# 08E-005.net
KiCad netlist of a schematic drawn in EAGLE
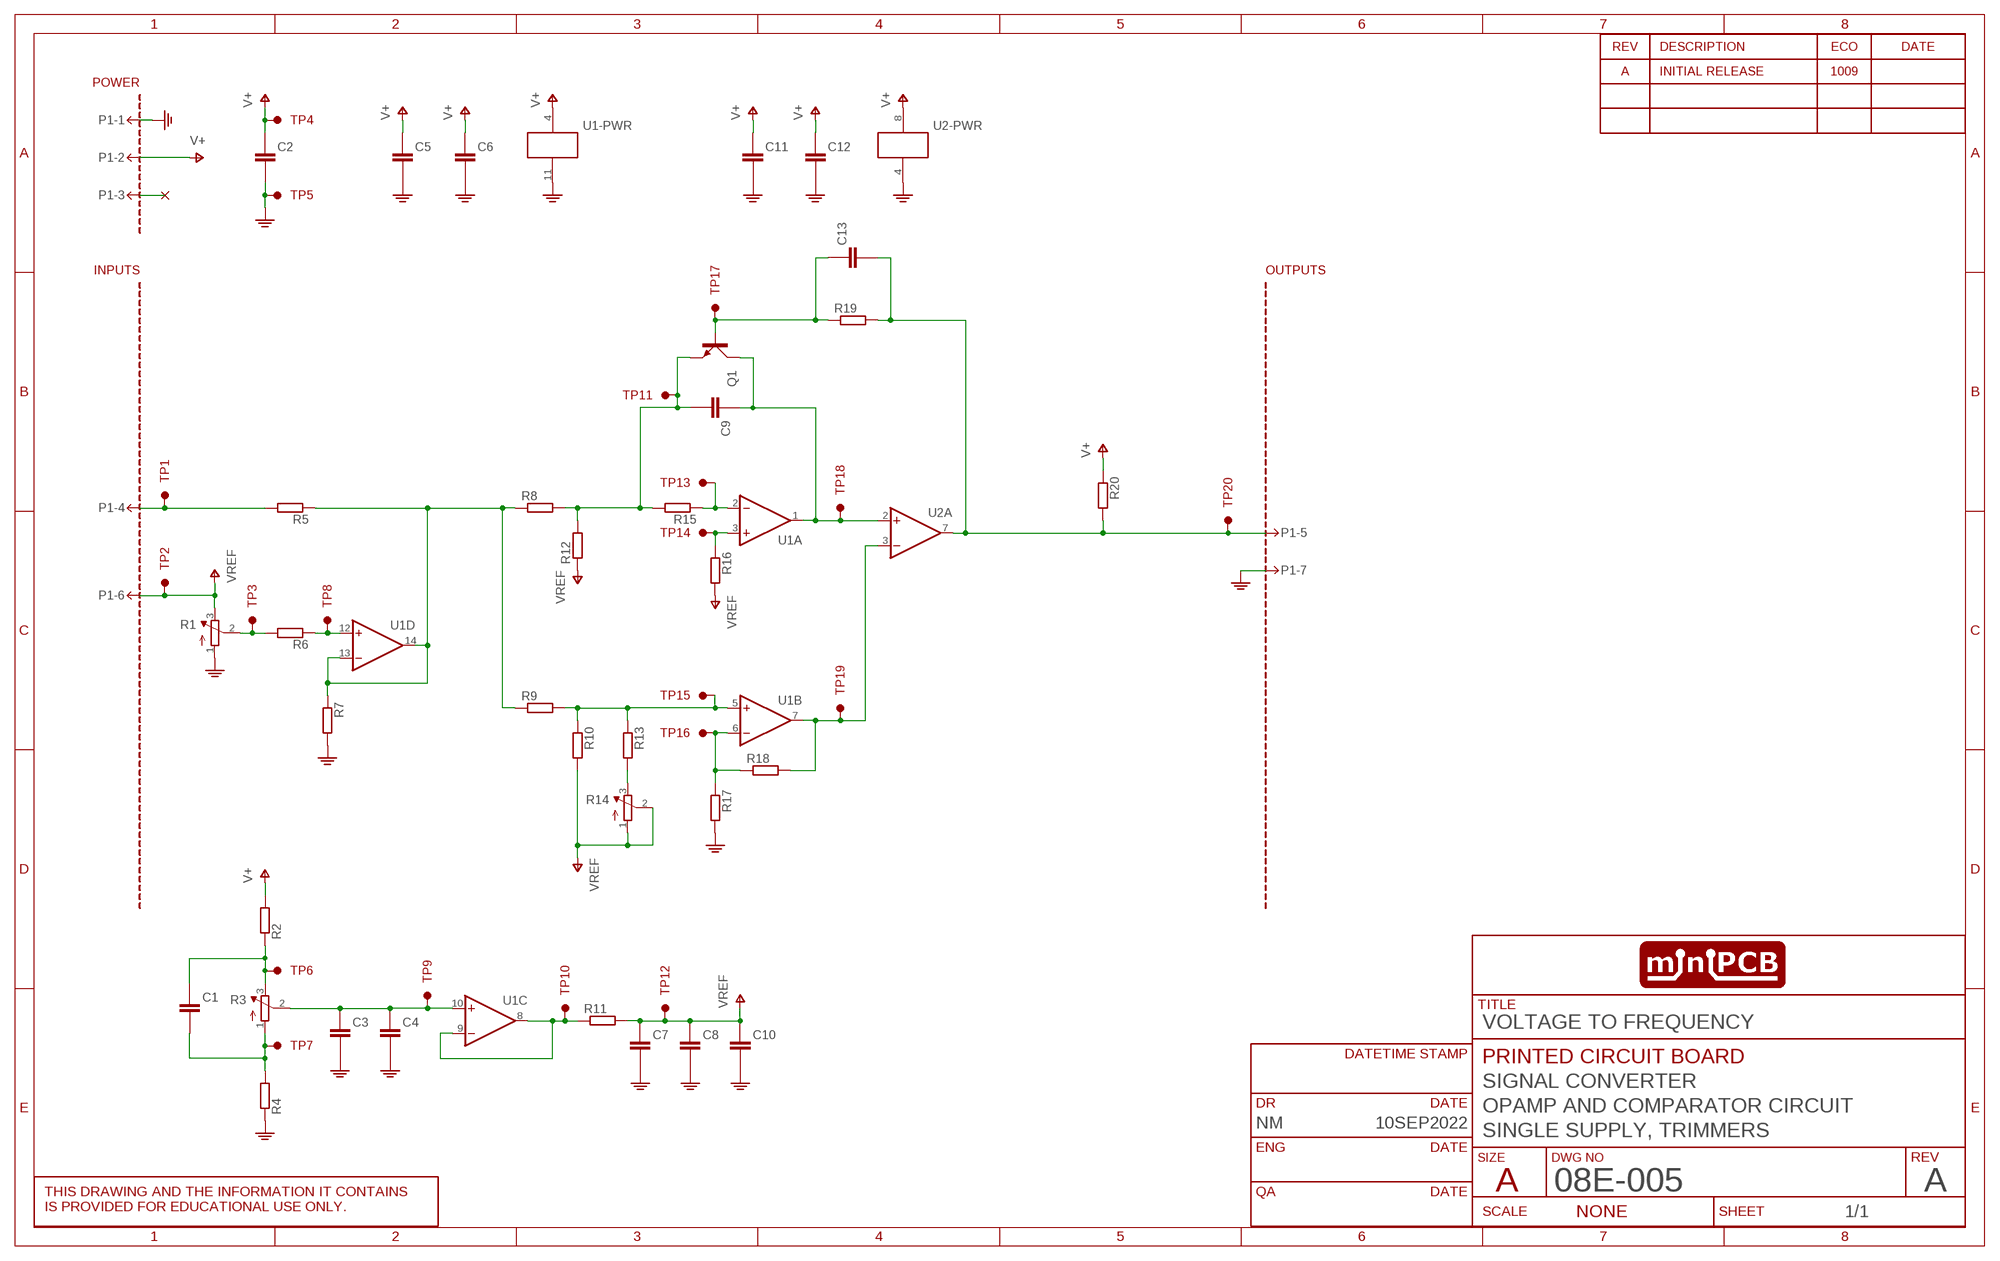
[diagram p0: schematic, sheet 1]

(export (version "E")
  (design (tool "Eeschema 10.0.6"))
  (components
    (comp (ref "C1")
      (value "CAPACITORTHD")
      (footprint "eagle-import:C050-024X044")
      (libsource (lib "eagle-import") (part "CAPACITORTHD"))
    )
    (comp (ref "C2")
      (value "CAPACITOR_10")
      (footprint "eagle-import:C5MM")
      (libsource (lib "eagle-import") (part "CAPACITOR_10"))
    )
    (comp (ref "C3")
      (value "CAPACITORTHD")
      (footprint "eagle-import:C050-024X044")
      (libsource (lib "eagle-import") (part "CAPACITORTHD"))
    )
    (comp (ref "C4")
      (value "CAPACITORTHD")
      (footprint "eagle-import:C050-024X044")
      (libsource (lib "eagle-import") (part "CAPACITORTHD"))
    )
    (comp (ref "C5")
      (value "CAPACITORTHD")
      (footprint "eagle-import:C050-024X044")
      (libsource (lib "eagle-import") (part "CAPACITORTHD"))
    )
    (comp (ref "C6")
      (value "CAPACITORTHD")
      (footprint "eagle-import:C050-024X044")
      (libsource (lib "eagle-import") (part "CAPACITORTHD"))
    )
    (comp (ref "C7")
      (value "CAPACITORTHD")
      (footprint "eagle-import:C050-024X044")
      (libsource (lib "eagle-import") (part "CAPACITORTHD"))
    )
    (comp (ref "C8")
      (value "CAPACITORTHD")
      (footprint "eagle-import:C050-024X044")
      (libsource (lib "eagle-import") (part "CAPACITORTHD"))
    )
    (comp (ref "C9")
      (value "CAPACITORTHD")
      (footprint "eagle-import:C050-024X044")
      (libsource (lib "eagle-import") (part "CAPACITORTHD"))
    )
    (comp (ref "C10")
      (value "CAPACITOR_10")
      (footprint "eagle-import:C5MM")
      (libsource (lib "eagle-import") (part "CAPACITOR_10"))
    )
    (comp (ref "C11")
      (value "CAPACITORTHD")
      (footprint "eagle-import:C050-024X044")
      (libsource (lib "eagle-import") (part "CAPACITORTHD"))
    )
    (comp (ref "C12")
      (value "CAPACITORTHD")
      (footprint "eagle-import:C050-024X044")
      (libsource (lib "eagle-import") (part "CAPACITORTHD"))
    )
    (comp (ref "C13")
      (value "CAPACITORTHD")
      (footprint "eagle-import:C050-024X044")
      (libsource (lib "eagle-import") (part "CAPACITORTHD"))
    )
    (comp (ref "P1-")
      (value "MINIPCB_7P50X100")
      (footprint "eagle-import:MINIPCB_7P_50X100")
      (fields (field (name "PART_NUMBER") "X08E-005-A"))
      (libsource (lib "eagle-import") (part "MINIPCB_7P50X100"))
    )
    (comp (ref "Q1")
      (value "BJT_NPNEBC")
      (footprint "eagle-import:TO92-EBC-OVAL")
      (libsource (lib "eagle-import") (part "BJT_NPNEBC"))
    )
    (comp (ref "R1")
      (value "TRIMPOT3386")
      (footprint "eagle-import:TRIM-3386")
      (libsource (lib "eagle-import") (part "TRIMPOT3386"))
    )
    (comp (ref "R2")
      (value "RESISTOR10MM")
      (footprint "eagle-import:0207_10")
      (libsource (lib "eagle-import") (part "RESISTOR10MM"))
    )
    (comp (ref "R3")
      (value "TRIMPOT0.100THD")
      (footprint "eagle-import:TRIM_0100")
      (libsource (lib "eagle-import") (part "TRIMPOT0.100THD"))
    )
    (comp (ref "R4")
      (value "RESISTOR10MM")
      (footprint "eagle-import:0207_10")
      (libsource (lib "eagle-import") (part "RESISTOR10MM"))
    )
    (comp (ref "R5")
      (value "RESISTOR10MM")
      (footprint "eagle-import:0207_10")
      (libsource (lib "eagle-import") (part "RESISTOR10MM"))
    )
    (comp (ref "R6")
      (value "RESISTOR10MM")
      (footprint "eagle-import:0207_10")
      (libsource (lib "eagle-import") (part "RESISTOR10MM"))
    )
    (comp (ref "R7")
      (value "RESISTOR10MM")
      (footprint "eagle-import:0207_10")
      (libsource (lib "eagle-import") (part "RESISTOR10MM"))
    )
    (comp (ref "R8")
      (value "RESISTOR10MM")
      (footprint "eagle-import:0207_10")
      (libsource (lib "eagle-import") (part "RESISTOR10MM"))
    )
    (comp (ref "R9")
      (value "RESISTOR10MM")
      (footprint "eagle-import:0207_10")
      (libsource (lib "eagle-import") (part "RESISTOR10MM"))
    )
    (comp (ref "R10")
      (value "RESISTOR10MM")
      (footprint "eagle-import:0207_10")
      (libsource (lib "eagle-import") (part "RESISTOR10MM"))
    )
    (comp (ref "R11")
      (value "RESISTOR10MM")
      (footprint "eagle-import:0207_10")
      (libsource (lib "eagle-import") (part "RESISTOR10MM"))
    )
    (comp (ref "R12")
      (value "RESISTOR10MM")
      (footprint "eagle-import:0207_10")
      (libsource (lib "eagle-import") (part "RESISTOR10MM"))
    )
    (comp (ref "R13")
      (value "RESISTOR10MM")
      (footprint "eagle-import:0207_10")
      (libsource (lib "eagle-import") (part "RESISTOR10MM"))
    )
    (comp (ref "R14")
      (value "TRIMPOT0.100THD")
      (footprint "eagle-import:TRIM_0100")
      (libsource (lib "eagle-import") (part "TRIMPOT0.100THD"))
    )
    (comp (ref "R15")
      (value "RESISTOR10MM")
      (footprint "eagle-import:0207_10")
      (libsource (lib "eagle-import") (part "RESISTOR10MM"))
    )
    (comp (ref "R16")
      (value "RESISTOR10MM")
      (footprint "eagle-import:0207_10")
      (libsource (lib "eagle-import") (part "RESISTOR10MM"))
    )
    (comp (ref "R17")
      (value "RESISTOR10MM")
      (footprint "eagle-import:0207_10")
      (libsource (lib "eagle-import") (part "RESISTOR10MM"))
    )
    (comp (ref "R18")
      (value "RESISTOR10MM")
      (footprint "eagle-import:0207_10")
      (libsource (lib "eagle-import") (part "RESISTOR10MM"))
    )
    (comp (ref "R19")
      (value "RESISTOR10MM")
      (footprint "eagle-import:0207_10")
      (libsource (lib "eagle-import") (part "RESISTOR10MM"))
    )
    (comp (ref "R20")
      (value "RESISTOR10MM")
      (footprint "eagle-import:0207_10")
      (libsource (lib "eagle-import") (part "RESISTOR10MM"))
    )
    (comp (ref "TP1")
      (value "TESTPOINTKE5000-SMTEXT")
      (footprint "eagle-import:PINS_1_TESTPOINT_KE5000_NOTEXT")
      (libsource (lib "eagle-import") (part "TESTPOINTKE5000-SMTEXT"))
    )
    (comp (ref "TP2")
      (value "TESTPOINTKE5000-SMTEXT")
      (footprint "eagle-import:PINS_1_TESTPOINT_KE5000_NOTEXT")
      (libsource (lib "eagle-import") (part "TESTPOINTKE5000-SMTEXT"))
    )
    (comp (ref "TP3")
      (value "TESTPOINTKE5000-SMTEXT")
      (footprint "eagle-import:PINS_1_TESTPOINT_KE5000_NOTEXT")
      (libsource (lib "eagle-import") (part "TESTPOINTKE5000-SMTEXT"))
    )
    (comp (ref "TP4")
      (value "TESTPOINTKE5000-SMTEXT")
      (footprint "eagle-import:PINS_1_TESTPOINT_KE5000_NOTEXT")
      (libsource (lib "eagle-import") (part "TESTPOINTKE5000-SMTEXT"))
    )
    (comp (ref "TP5")
      (value "TESTPOINTKE5000-SMTEXT")
      (footprint "eagle-import:PINS_1_TESTPOINT_KE5000_NOTEXT")
      (libsource (lib "eagle-import") (part "TESTPOINTKE5000-SMTEXT"))
    )
    (comp (ref "TP6")
      (value "TESTPOINTKE5000-SMTEXT")
      (footprint "eagle-import:PINS_1_TESTPOINT_KE5000_NOTEXT")
      (libsource (lib "eagle-import") (part "TESTPOINTKE5000-SMTEXT"))
    )
    (comp (ref "TP7")
      (value "TESTPOINTKE5000-SMTEXT")
      (footprint "eagle-import:PINS_1_TESTPOINT_KE5000_NOTEXT")
      (libsource (lib "eagle-import") (part "TESTPOINTKE5000-SMTEXT"))
    )
    (comp (ref "TP8")
      (value "TESTPOINTKE5000-SMTEXT")
      (footprint "eagle-import:PINS_1_TESTPOINT_KE5000_NOTEXT")
      (libsource (lib "eagle-import") (part "TESTPOINTKE5000-SMTEXT"))
    )
    (comp (ref "TP9")
      (value "TESTPOINTKE5000-SMTEXT")
      (footprint "eagle-import:PINS_1_TESTPOINT_KE5000_NOTEXT")
      (libsource (lib "eagle-import") (part "TESTPOINTKE5000-SMTEXT"))
    )
    (comp (ref "TP10")
      (value "TESTPOINTKE5000-SMTEXT")
      (footprint "eagle-import:PINS_1_TESTPOINT_KE5000_NOTEXT")
      (libsource (lib "eagle-import") (part "TESTPOINTKE5000-SMTEXT"))
    )
    (comp (ref "TP11")
      (value "TESTPOINTKE5000-SMTEXT")
      (footprint "eagle-import:PINS_1_TESTPOINT_KE5000_NOTEXT")
      (libsource (lib "eagle-import") (part "TESTPOINTKE5000-SMTEXT"))
    )
    (comp (ref "TP12")
      (value "TESTPOINTKE5000-SMTEXT")
      (footprint "eagle-import:PINS_1_TESTPOINT_KE5000_NOTEXT")
      (libsource (lib "eagle-import") (part "TESTPOINTKE5000-SMTEXT"))
    )
    (comp (ref "TP13")
      (value "TESTPOINTKE5000-SMTEXT")
      (footprint "eagle-import:PINS_1_TESTPOINT_KE5000_NOTEXT")
      (libsource (lib "eagle-import") (part "TESTPOINTKE5000-SMTEXT"))
    )
    (comp (ref "TP14")
      (value "TESTPOINTKE5000-SMTEXT")
      (footprint "eagle-import:PINS_1_TESTPOINT_KE5000_NOTEXT")
      (libsource (lib "eagle-import") (part "TESTPOINTKE5000-SMTEXT"))
    )
    (comp (ref "TP15")
      (value "TESTPOINTKE5000-SMTEXT")
      (footprint "eagle-import:PINS_1_TESTPOINT_KE5000_NOTEXT")
      (libsource (lib "eagle-import") (part "TESTPOINTKE5000-SMTEXT"))
    )
    (comp (ref "TP16")
      (value "TESTPOINTKE5000-SMTEXT")
      (footprint "eagle-import:PINS_1_TESTPOINT_KE5000_NOTEXT")
      (libsource (lib "eagle-import") (part "TESTPOINTKE5000-SMTEXT"))
    )
    (comp (ref "TP17")
      (value "TESTPOINTKE5000-SMTEXT")
      (footprint "eagle-import:PINS_1_TESTPOINT_KE5000_NOTEXT")
      (libsource (lib "eagle-import") (part "TESTPOINTKE5000-SMTEXT"))
    )
    (comp (ref "TP18")
      (value "TESTPOINTKE5000-SMTEXT")
      (footprint "eagle-import:PINS_1_TESTPOINT_KE5000_NOTEXT")
      (libsource (lib "eagle-import") (part "TESTPOINTKE5000-SMTEXT"))
    )
    (comp (ref "TP19")
      (value "TESTPOINTKE5000-SMTEXT")
      (footprint "eagle-import:PINS_1_TESTPOINT_KE5000_NOTEXT")
      (libsource (lib "eagle-import") (part "TESTPOINTKE5000-SMTEXT"))
    )
    (comp (ref "TP20")
      (value "TESTPOINTKE5000-SMTEXT")
      (footprint "eagle-import:PINS_1_TESTPOINT_KE5000_NOTEXT")
      (libsource (lib "eagle-import") (part "TESTPOINTKE5000-SMTEXT"))
    )
    (comp (ref "U1")
      (value "OPAMP_QUADTHD")
      (footprint "eagle-import:DIL14")
      (libsource (lib "eagle-import") (part "OPAMP_QUADTHD"))
    )
    (comp (ref "U2")
      (value "COMPARATOR_SINGLE_WITHBALANCETHD")
      (footprint "eagle-import:DIL08")
      (libsource (lib "eagle-import") (part "COMPARATOR_SINGLE_WITHBALANCETHD"))
    )
  )
  (nets
    (net (code "1") (name "GND") (class "Default")
      (node (ref "C10") (pin "-") (pinfunction "-_-") (pintype "passive"))
      (node (ref "C11") (pin "2") (pinfunction "-_2") (pintype "passive"))
      (node (ref "C12") (pin "2") (pinfunction "-_2") (pintype "passive"))
      (node (ref "C2") (pin "-") (pinfunction "-_-") (pintype "passive"))
      (node (ref "C3") (pin "2") (pinfunction "-_2") (pintype "passive"))
      (node (ref "C4") (pin "2") (pinfunction "-_2") (pintype "passive"))
      (node (ref "C5") (pin "2") (pinfunction "-_2") (pintype "passive"))
      (node (ref "C6") (pin "2") (pinfunction "-_2") (pintype "passive"))
      (node (ref "C7") (pin "2") (pinfunction "-_2") (pintype "passive"))
      (node (ref "C8") (pin "2") (pinfunction "-_2") (pintype "passive"))
      (node (ref "P1-") (pin "1") (pinfunction "1_1") (pintype "bidirectional"))
      (node (ref "P1-") (pin "7") (pinfunction "1_7") (pintype "bidirectional"))
      (node (ref "R1") (pin "1") (pinfunction "A_1") (pintype "passive"))
      (node (ref "R17") (pin "2") (pinfunction "2_2") (pintype "passive"))
      (node (ref "R4") (pin "1") (pinfunction "1_1") (pintype "passive"))
      (node (ref "R7") (pin "2") (pinfunction "2_2") (pintype "passive"))
      (node (ref "TP5") (pin "1") (pinfunction "1_1") (pintype "bidirectional"))
      (node (ref "U1") (pin "11") (pinfunction "V-_11") (pintype "power_in"))
      (node (ref "U2") (pin "4") (pinfunction "V-_4") (pintype "power_in"))
    )
    (net (code "2") (name "Net-(C1-+)") (class "Default")
      (node (ref "C1") (pin "1") (pinfunction "+_1") (pintype "passive"))
      (node (ref "R2") (pin "1") (pinfunction "1_1") (pintype "passive"))
      (node (ref "R3") (pin "3") (pinfunction "E_3") (pintype "passive"))
      (node (ref "TP6") (pin "1") (pinfunction "1_1") (pintype "bidirectional"))
    )
    (net (code "3") (name "Net-(C1--)") (class "Default")
      (node (ref "C1") (pin "2") (pinfunction "-_2") (pintype "passive"))
      (node (ref "R3") (pin "1") (pinfunction "A_1") (pintype "passive"))
      (node (ref "R4") (pin "2") (pinfunction "2_2") (pintype "passive"))
      (node (ref "TP7") (pin "1") (pinfunction "1_1") (pintype "bidirectional"))
    )
    (net (code "4") (name "Net-(C3-+)") (class "Default")
      (node (ref "C3") (pin "1") (pinfunction "+_1") (pintype "passive"))
      (node (ref "C4") (pin "1") (pinfunction "+_1") (pintype "passive"))
      (node (ref "R3") (pin "2") (pinfunction "S_2") (pintype "passive"))
      (node (ref "TP9") (pin "1") (pinfunction "1_1") (pintype "bidirectional"))
      (node (ref "U1") (pin "10") (pinfunction "+IN_10") (pintype "input"))
    )
    (net (code "5") (name "Net-(C9-+)") (class "Default")
      (node (ref "C9") (pin "1") (pinfunction "+_1") (pintype "passive"))
      (node (ref "Q1") (pin "C") (pinfunction "C_C") (pintype "passive"))
      (node (ref "TP18") (pin "1") (pinfunction "1_1") (pintype "bidirectional"))
      (node (ref "U1") (pin "1") (pinfunction "OUT_1") (pintype "output"))
      (node (ref "U2") (pin "2") (pinfunction "+IN_2") (pintype "input"))
    )
    (net (code "6") (name "Net-(C9--)") (class "Default")
      (node (ref "C9") (pin "2") (pinfunction "-_2") (pintype "passive"))
      (node (ref "Q1") (pin "E") (pinfunction "E_E") (pintype "passive"))
      (node (ref "R12") (pin "2") (pinfunction "2_2") (pintype "passive"))
      (node (ref "R15") (pin "2") (pinfunction "2_2") (pintype "passive"))
      (node (ref "R8") (pin "2") (pinfunction "2_2") (pintype "passive"))
      (node (ref "TP11") (pin "1") (pinfunction "1_1") (pintype "bidirectional"))
    )
    (net (code "7") (name "Net-(C13-+)") (class "Default")
      (node (ref "C13") (pin "1") (pinfunction "+_1") (pintype "passive"))
      (node (ref "Q1") (pin "B") (pinfunction "B_B") (pintype "passive"))
      (node (ref "R19") (pin "1") (pinfunction "1_1") (pintype "passive"))
      (node (ref "TP17") (pin "1") (pinfunction "1_1") (pintype "bidirectional"))
    )
    (net (code "8") (name "Net-(C13--)") (class "Default")
      (node (ref "C13") (pin "2") (pinfunction "-_2") (pintype "passive"))
      (node (ref "P1-") (pin "5") (pinfunction "1_5") (pintype "bidirectional"))
      (node (ref "R19") (pin "2") (pinfunction "2_2") (pintype "passive"))
      (node (ref "R20") (pin "2") (pinfunction "2_2") (pintype "passive"))
      (node (ref "TP20") (pin "1") (pinfunction "1_1") (pintype "bidirectional"))
      (node (ref "U2") (pin "7") (pinfunction "OUT_7") (pintype "output"))
    )
    (net (code "9") (name "Net-(P1-D-1)") (class "Default")
      (node (ref "P1-") (pin "4") (pinfunction "1_4") (pintype "bidirectional"))
      (node (ref "R5") (pin "2") (pinfunction "2_2") (pintype "passive"))
      (node (ref "TP1") (pin "1") (pinfunction "1_1") (pintype "bidirectional"))
    )
    (net (code "10") (name "Net-(R1-S)") (class "Default")
      (node (ref "R1") (pin "2") (pinfunction "S_2") (pintype "passive"))
      (node (ref "R6") (pin "2") (pinfunction "2_2") (pintype "passive"))
      (node (ref "TP3") (pin "1") (pinfunction "1_1") (pintype "bidirectional"))
    )
    (net (code "11") (name "Net-(R14-E)") (class "Default")
      (node (ref "R13") (pin "2") (pinfunction "2_2") (pintype "passive"))
      (node (ref "R14") (pin "3") (pinfunction "E_3") (pintype "passive"))
    )
    (net (code "12") (name "Net-(U1B-+IN)") (class "Default")
      (node (ref "R16") (pin "1") (pinfunction "1_1") (pintype "passive"))
      (node (ref "TP14") (pin "1") (pinfunction "1_1") (pintype "bidirectional"))
      (node (ref "U1") (pin "3") (pinfunction "+IN_3") (pintype "input"))
    )
    (net (code "13") (name "Net-(U1B--IN)") (class "Default")
      (node (ref "R15") (pin "1") (pinfunction "1_1") (pintype "passive"))
      (node (ref "TP13") (pin "1") (pinfunction "1_1") (pintype "bidirectional"))
      (node (ref "U1") (pin "2") (pinfunction "-IN_2") (pintype "input"))
    )
    (net (code "14") (name "Net-(U1C-+IN)") (class "Default")
      (node (ref "R10") (pin "1") (pinfunction "1_1") (pintype "passive"))
      (node (ref "R13") (pin "1") (pinfunction "1_1") (pintype "passive"))
      (node (ref "R9") (pin "2") (pinfunction "2_2") (pintype "passive"))
      (node (ref "TP15") (pin "1") (pinfunction "1_1") (pintype "bidirectional"))
      (node (ref "U1") (pin "5") (pinfunction "+IN_5") (pintype "input"))
    )
    (net (code "15") (name "Net-(U1C--IN)") (class "Default")
      (node (ref "R17") (pin "1") (pinfunction "1_1") (pintype "passive"))
      (node (ref "R18") (pin "1") (pinfunction "1_1") (pintype "passive"))
      (node (ref "TP16") (pin "1") (pinfunction "1_1") (pintype "bidirectional"))
      (node (ref "U1") (pin "6") (pinfunction "-IN_6") (pintype "input"))
    )
    (net (code "16") (name "Net-(U1C-OUT)") (class "Default")
      (node (ref "R18") (pin "2") (pinfunction "2_2") (pintype "passive"))
      (node (ref "TP19") (pin "1") (pinfunction "1_1") (pintype "bidirectional"))
      (node (ref "U1") (pin "7") (pinfunction "OUT_7") (pintype "output"))
      (node (ref "U2") (pin "3") (pinfunction "-IN_3") (pintype "input"))
    )
    (net (code "17") (name "Net-(U1D--IN)") (class "Default")
      (node (ref "R11") (pin "1") (pinfunction "1_1") (pintype "passive"))
      (node (ref "TP10") (pin "1") (pinfunction "1_1") (pintype "bidirectional"))
      (node (ref "U1") (pin "8") (pinfunction "OUT_8") (pintype "output"))
      (node (ref "U1") (pin "9") (pinfunction "-IN_9") (pintype "input"))
    )
    (net (code "18") (name "Net-(U1E-+IN)") (class "Default")
      (node (ref "R6") (pin "1") (pinfunction "1_1") (pintype "passive"))
      (node (ref "TP8") (pin "1") (pinfunction "1_1") (pintype "bidirectional"))
      (node (ref "U1") (pin "12") (pinfunction "+IN_12") (pintype "input"))
    )
    (net (code "19") (name "Net-(U1E--IN)") (class "Default")
      (node (ref "R5") (pin "1") (pinfunction "1_1") (pintype "passive"))
      (node (ref "R7") (pin "1") (pinfunction "1_1") (pintype "passive"))
      (node (ref "R8") (pin "1") (pinfunction "1_1") (pintype "passive"))
      (node (ref "R9") (pin "1") (pinfunction "1_1") (pintype "passive"))
      (node (ref "U1") (pin "13") (pinfunction "-IN_13") (pintype "input"))
      (node (ref "U1") (pin "14") (pinfunction "OUT_14") (pintype "output"))
    )
    (net (code "20") (name "V+") (class "Default")
      (node (ref "C11") (pin "1") (pinfunction "+_1") (pintype "passive"))
      (node (ref "C12") (pin "1") (pinfunction "+_1") (pintype "passive"))
      (node (ref "C2") (pin "+") (pinfunction "+_+") (pintype "passive"))
      (node (ref "C5") (pin "1") (pinfunction "+_1") (pintype "passive"))
      (node (ref "C6") (pin "1") (pinfunction "+_1") (pintype "passive"))
      (node (ref "P1-") (pin "2") (pinfunction "1_2") (pintype "bidirectional"))
      (node (ref "R2") (pin "2") (pinfunction "2_2") (pintype "passive"))
      (node (ref "R20") (pin "1") (pinfunction "1_1") (pintype "passive"))
      (node (ref "TP4") (pin "1") (pinfunction "1_1") (pintype "bidirectional"))
      (node (ref "U1") (pin "4") (pinfunction "V+_4") (pintype "power_in"))
      (node (ref "U2") (pin "8") (pinfunction "V+_8") (pintype "power_in"))
    )
    (net (code "21") (name "VREF") (class "Default")
      (node (ref "C10") (pin "+") (pinfunction "+_+") (pintype "passive"))
      (node (ref "C7") (pin "1") (pinfunction "+_1") (pintype "passive"))
      (node (ref "C8") (pin "1") (pinfunction "+_1") (pintype "passive"))
      (node (ref "P1-") (pin "6") (pinfunction "1_6") (pintype "bidirectional"))
      (node (ref "R1") (pin "3") (pinfunction "E_3") (pintype "passive"))
      (node (ref "R10") (pin "2") (pinfunction "2_2") (pintype "passive"))
      (node (ref "R11") (pin "2") (pinfunction "2_2") (pintype "passive"))
      (node (ref "R12") (pin "1") (pinfunction "1_1") (pintype "passive"))
      (node (ref "R14") (pin "1") (pinfunction "A_1") (pintype "passive"))
      (node (ref "R14") (pin "2") (pinfunction "S_2") (pintype "passive"))
      (node (ref "R16") (pin "2") (pinfunction "2_2") (pintype "passive"))
      (node (ref "TP12") (pin "1") (pinfunction "1_1") (pintype "bidirectional"))
      (node (ref "TP2") (pin "1") (pinfunction "1_1") (pintype "bidirectional"))
    )
    (net (code "22") (name "unconnected-(P1-C-1-Pad3)") (class "Default")
      (node (ref "P1-") (pin "3") (pinfunction "1_3") (pintype "bidirectional"))
    )
  )
)
